# design.net
KiCad netlist of a schematic drawn in EasyEDA Pro
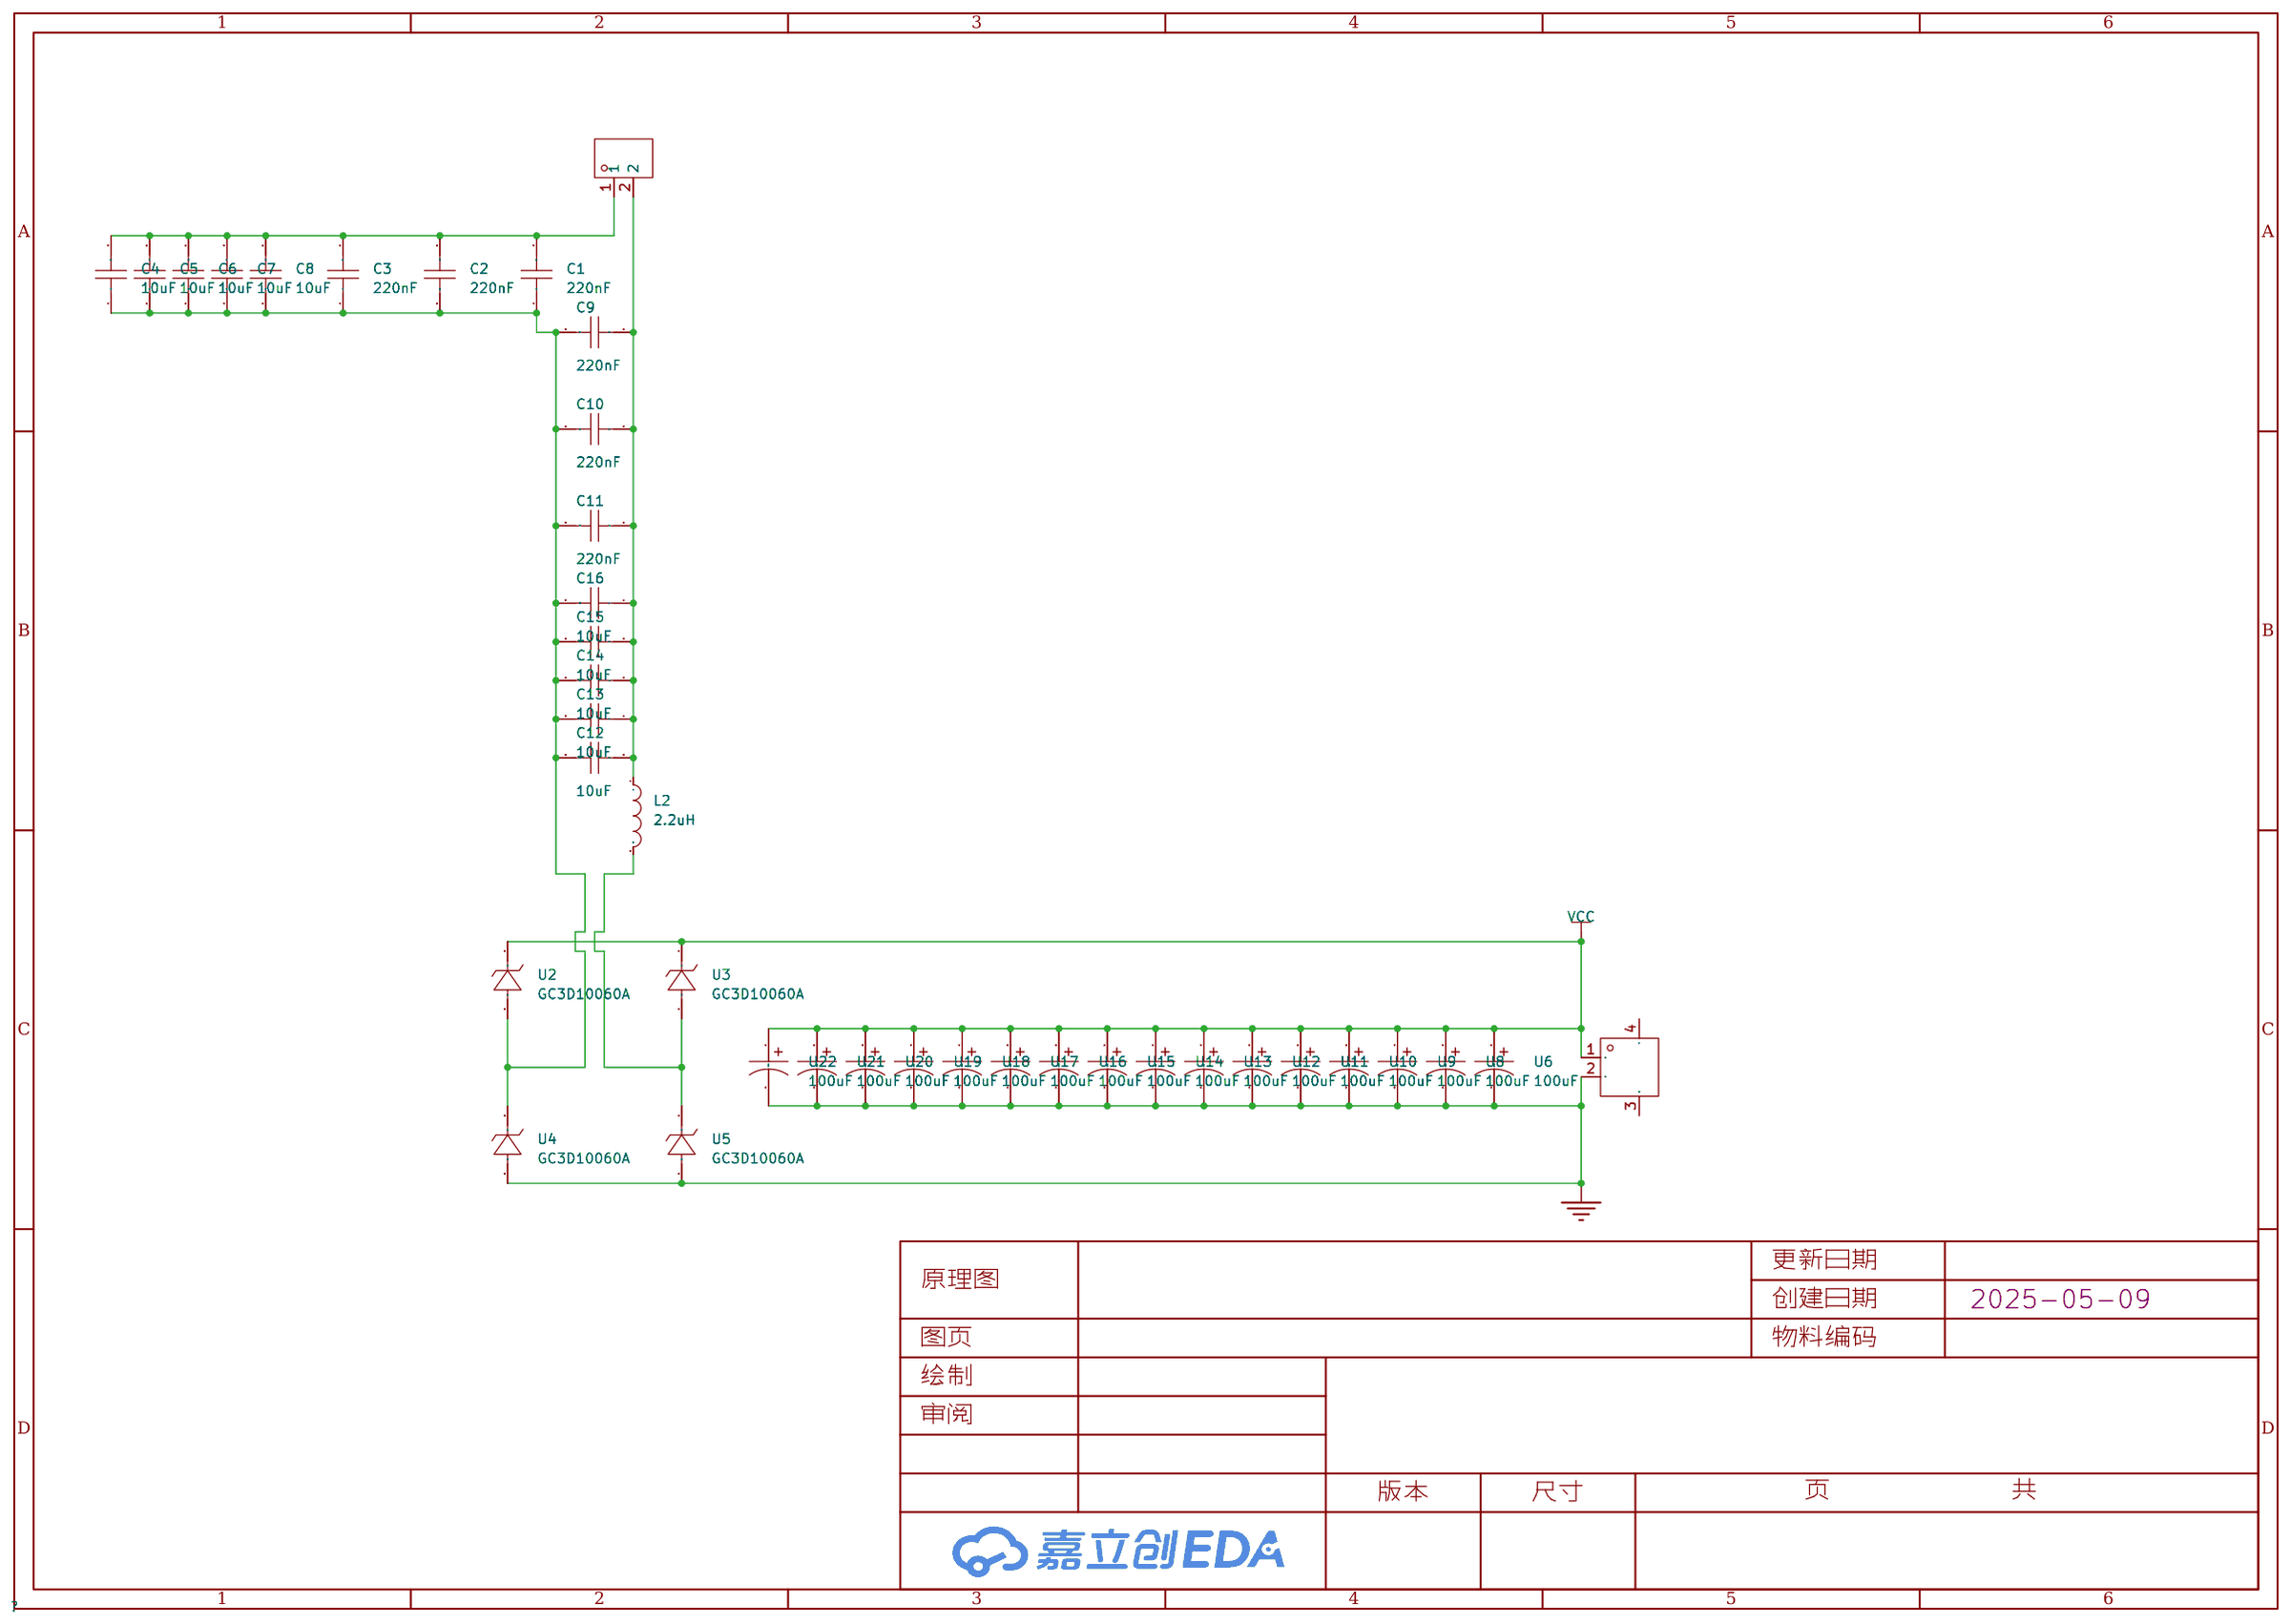
[diagram p0: schematic sheet]

(export (version "E")
  (design (tool "Eeschema 10.0.6"))
  (components
    (comp (ref "C1")
      (value "220nF")
      (footprint "easyedapro:CAP-TH_L12.0-W6.5-P10.00-D1.0")
      (description "容值:220nF;精度:±5%;额定电压:630V;工作温度:-40°C~+105°C;")
      (fields
        (field (name "Manufacturer Part") "MPP224J2J10NN22600")
        (field (name "Manufacturer") "KNSCHA(科尼盛)")
      )
      (libsource (lib "easyedapro") (part "MPP224J2J10NN22600"))
    )
    (comp (ref "C2")
      (value "220nF")
      (footprint "easyedapro:CAP-TH_L12.0-W6.5-P10.00-D1.0")
      (description "容值:220nF;精度:±5%;额定电压:630V;工作温度:-40°C~+105°C;")
      (fields
        (field (name "Manufacturer Part") "MPP224J2J10NN22600")
        (field (name "Manufacturer") "KNSCHA(科尼盛)")
      )
      (libsource (lib "easyedapro") (part "MPP224J2J10NN22600"))
    )
    (comp (ref "C3")
      (value "220nF")
      (footprint "easyedapro:CAP-TH_L12.0-W6.5-P10.00-D1.0")
      (description "容值:220nF;精度:±5%;额定电压:630V;工作温度:-40°C~+105°C;")
      (fields
        (field (name "Manufacturer Part") "MPP224J2J10NN22600")
        (field (name "Manufacturer") "KNSCHA(科尼盛)")
      )
      (libsource (lib "easyedapro") (part "MPP224J2J10NN22600"))
    )
    (comp (ref "C4")
      (value "10uF")
      (footprint "easyedapro:C1206")
      (description "容值:10uF;精度:±10%;额定电压:50V;温度系数:X5R;")
      (fields
        (field (name "Manufacturer Part") "HGC1206R5106K500NSPJ")
        (field (name "Manufacturer") "Chinocera(华瓷)")
      )
      (libsource (lib "easyedapro") (part "HGC1206R5106K500NSPJ"))
    )
    (comp (ref "C5")
      (value "10uF")
      (footprint "easyedapro:C1206")
      (description "容值:10uF;精度:±10%;额定电压:50V;温度系数:X5R;")
      (fields
        (field (name "Manufacturer Part") "HGC1206R5106K500NSPJ")
        (field (name "Manufacturer") "Chinocera(华瓷)")
      )
      (libsource (lib "easyedapro") (part "HGC1206R5106K500NSPJ"))
    )
    (comp (ref "C6")
      (value "10uF")
      (footprint "easyedapro:C1206")
      (description "容值:10uF;精度:±10%;额定电压:50V;温度系数:X5R;")
      (fields
        (field (name "Manufacturer Part") "HGC1206R5106K500NSPJ")
        (field (name "Manufacturer") "Chinocera(华瓷)")
      )
      (libsource (lib "easyedapro") (part "HGC1206R5106K500NSPJ"))
    )
    (comp (ref "C7")
      (value "10uF")
      (footprint "easyedapro:C1206")
      (description "容值:10uF;精度:±10%;额定电压:50V;温度系数:X5R;")
      (fields
        (field (name "Manufacturer Part") "HGC1206R5106K500NSPJ")
        (field (name "Manufacturer") "Chinocera(华瓷)")
      )
      (libsource (lib "easyedapro") (part "HGC1206R5106K500NSPJ"))
    )
    (comp (ref "C8")
      (value "10uF")
      (footprint "easyedapro:C1206")
      (description "容值:10uF;精度:±10%;额定电压:50V;温度系数:X5R;")
      (fields
        (field (name "Manufacturer Part") "HGC1206R5106K500NSPJ")
        (field (name "Manufacturer") "Chinocera(华瓷)")
      )
      (libsource (lib "easyedapro") (part "HGC1206R5106K500NSPJ"))
    )
    (comp (ref "C9")
      (value "220nF")
      (footprint "easyedapro:CAP-TH_L12.0-W6.5-P10.00-D1.0")
      (description "容值:220nF;精度:±5%;额定电压:630V;工作温度:-40°C~+105°C;")
      (fields
        (field (name "Manufacturer Part") "MPP224J2J10NN22600")
        (field (name "Manufacturer") "KNSCHA(科尼盛)")
      )
      (libsource (lib "easyedapro") (part "MPP224J2J10NN22600"))
    )
    (comp (ref "C10")
      (value "220nF")
      (footprint "easyedapro:CAP-TH_L12.0-W6.5-P10.00-D1.0")
      (description "容值:220nF;精度:±5%;额定电压:630V;工作温度:-40°C~+105°C;")
      (fields
        (field (name "Manufacturer Part") "MPP224J2J10NN22600")
        (field (name "Manufacturer") "KNSCHA(科尼盛)")
      )
      (libsource (lib "easyedapro") (part "MPP224J2J10NN22600"))
    )
    (comp (ref "C11")
      (value "220nF")
      (footprint "easyedapro:CAP-TH_L12.0-W6.5-P10.00-D1.0")
      (description "容值:220nF;精度:±5%;额定电压:630V;工作温度:-40°C~+105°C;")
      (fields
        (field (name "Manufacturer Part") "MPP224J2J10NN22600")
        (field (name "Manufacturer") "KNSCHA(科尼盛)")
      )
      (libsource (lib "easyedapro") (part "MPP224J2J10NN22600"))
    )
    (comp (ref "C12")
      (value "10uF")
      (footprint "easyedapro:C1206")
      (description "容值:10uF;精度:±10%;额定电压:50V;温度系数:X5R;")
      (fields
        (field (name "Manufacturer Part") "HGC1206R5106K500NSPJ")
        (field (name "Manufacturer") "Chinocera(华瓷)")
      )
      (libsource (lib "easyedapro") (part "HGC1206R5106K500NSPJ"))
    )
    (comp (ref "C13")
      (value "10uF")
      (footprint "easyedapro:C1206")
      (description "容值:10uF;精度:±10%;额定电压:50V;温度系数:X5R;")
      (fields
        (field (name "Manufacturer Part") "HGC1206R5106K500NSPJ")
        (field (name "Manufacturer") "Chinocera(华瓷)")
      )
      (libsource (lib "easyedapro") (part "HGC1206R5106K500NSPJ"))
    )
    (comp (ref "C14")
      (value "10uF")
      (footprint "easyedapro:C1206")
      (description "容值:10uF;精度:±10%;额定电压:50V;温度系数:X5R;")
      (fields
        (field (name "Manufacturer Part") "HGC1206R5106K500NSPJ")
        (field (name "Manufacturer") "Chinocera(华瓷)")
      )
      (libsource (lib "easyedapro") (part "HGC1206R5106K500NSPJ"))
    )
    (comp (ref "C15")
      (value "10uF")
      (footprint "easyedapro:C1206")
      (description "容值:10uF;精度:±10%;额定电压:50V;温度系数:X5R;")
      (fields
        (field (name "Manufacturer Part") "HGC1206R5106K500NSPJ")
        (field (name "Manufacturer") "Chinocera(华瓷)")
      )
      (libsource (lib "easyedapro") (part "HGC1206R5106K500NSPJ"))
    )
    (comp (ref "C16")
      (value "10uF")
      (footprint "easyedapro:C1206")
      (description "容值:10uF;精度:±10%;额定电压:50V;温度系数:X5R;")
      (fields
        (field (name "Manufacturer Part") "HGC1206R5106K500NSPJ")
        (field (name "Manufacturer") "Chinocera(华瓷)")
      )
      (libsource (lib "easyedapro") (part "HGC1206R5106K500NSPJ"))
    )
    (comp (ref "CN1")
      (value "XT30U-M")
      (footprint "easyedapro:CONN-TH_XT30U-M")
      (description "类别:-;类型1:-;")
      (fields (field (name "Manufacturer") "AMASS(艾迈斯)"))
      (libsource (lib "easyedapro") (part "XT30U-M"))
    )
    (comp (ref "L2")
      (value "2.2uH")
      (footprint "easyedapro:IND-SMD_L11.0-W10.0")
      (description "电感值:2.2uH;精度:±20%;额定电流:13A;饱和电流(Isat):20A;类型:一体成型电感;")
      (fields
        (field (name "Manufacturer Part") "CXP1050-2R2M-AG(2.2uh)")
        (field (name "Manufacturer") "DMBJ(振宝佳)")
      )
      (libsource (lib "easyedapro") (part "CXP1050-2R2M-AG(2.2UH)"))
    )
    (comp (ref "U1")
      (value "XT30PW-F20.G.Y")
      (footprint "easyedapro:CONN-TH_XT30PW-F-1")
      (description "类别:-;类型1:-;")
      (fields (field (name "Manufacturer") "AMASS(艾迈斯)"))
      (libsource (lib "easyedapro") (part "XT30PW-F"))
    )
    (comp (ref "U2")
      (value "GC3D10060A")
      (footprint "easyedapro:TO-220-2_L10.2-W4.5-P5.08-L-A")
      (description "整流电流:30A;正向压降(Vf):1.5V;直流反向耐压(Vr):600V;")
      (fields (field (name "Manufacturer") "SUPSiC(国晶微半导体)"))
      (libsource (lib "easyedapro") (part "GC3D10060A"))
    )
    (comp (ref "U3")
      (value "GC3D10060A")
      (footprint "easyedapro:TO-220-2_L10.2-W4.5-P5.08-L-A")
      (description "整流电流:30A;正向压降(Vf):1.5V;直流反向耐压(Vr):600V;")
      (fields (field (name "Manufacturer") "SUPSiC(国晶微半导体)"))
      (libsource (lib "easyedapro") (part "GC3D10060A"))
    )
    (comp (ref "U4")
      (value "GC3D10060A")
      (footprint "easyedapro:TO-220-2_L10.2-W4.5-P5.08-L-A")
      (description "整流电流:30A;正向压降(Vf):1.5V;直流反向耐压(Vr):600V;")
      (fields (field (name "Manufacturer") "SUPSiC(国晶微半导体)"))
      (libsource (lib "easyedapro") (part "GC3D10060A"))
    )
    (comp (ref "U5")
      (value "GC3D10060A")
      (footprint "easyedapro:TO-220-2_L10.2-W4.5-P5.08-L-A")
      (description "整流电流:30A;正向压降(Vf):1.5V;直流反向耐压(Vr):600V;")
      (fields (field (name "Manufacturer") "SUPSiC(国晶微半导体)"))
      (libsource (lib "easyedapro") (part "GC3D10060A"))
    )
    (comp (ref "U6")
      (value "100uF")
      (footprint "easyedapro:CAP-TH_BD10.0-P5.00-D0.6-FD")
      (description "容值:100uF;精度:±20%;额定电压:100V;纹波电流:420mA@100kHz;等效串联电阻(ESR):420mΩ@100kHz;")
      (fields (field (name "Manufacturer Part") "01EC0961") (field (name "Manufacturer") "KNSCHA(科尼盛)"))
      (libsource (lib "easyedapro") (part "01EC0961"))
    )
    (comp (ref "U8")
      (value "100uF")
      (footprint "easyedapro:CAP-TH_BD10.0-P5.00-D0.6-FD")
      (description "容值:100uF;精度:±20%;额定电压:100V;纹波电流:420mA@100kHz;等效串联电阻(ESR):420mΩ@100kHz;")
      (fields (field (name "Manufacturer Part") "01EC0961") (field (name "Manufacturer") "KNSCHA(科尼盛)"))
      (libsource (lib "easyedapro") (part "01EC0961"))
    )
    (comp (ref "U9")
      (value "100uF")
      (footprint "easyedapro:CAP-TH_BD10.0-P5.00-D0.6-FD")
      (description "容值:100uF;精度:±20%;额定电压:100V;纹波电流:420mA@100kHz;等效串联电阻(ESR):420mΩ@100kHz;")
      (fields (field (name "Manufacturer Part") "01EC0961") (field (name "Manufacturer") "KNSCHA(科尼盛)"))
      (libsource (lib "easyedapro") (part "01EC0961"))
    )
    (comp (ref "U10")
      (value "100uF")
      (footprint "easyedapro:CAP-TH_BD10.0-P5.00-D0.6-FD")
      (description "容值:100uF;精度:±20%;额定电压:100V;纹波电流:420mA@100kHz;等效串联电阻(ESR):420mΩ@100kHz;")
      (fields (field (name "Manufacturer Part") "01EC0961") (field (name "Manufacturer") "KNSCHA(科尼盛)"))
      (libsource (lib "easyedapro") (part "01EC0961"))
    )
    (comp (ref "U11")
      (value "100uF")
      (footprint "easyedapro:CAP-TH_BD10.0-P5.00-D0.6-FD")
      (description "容值:100uF;精度:±20%;额定电压:100V;纹波电流:420mA@100kHz;等效串联电阻(ESR):420mΩ@100kHz;")
      (fields (field (name "Manufacturer Part") "01EC0961") (field (name "Manufacturer") "KNSCHA(科尼盛)"))
      (libsource (lib "easyedapro") (part "01EC0961"))
    )
    (comp (ref "U12")
      (value "100uF")
      (footprint "easyedapro:CAP-TH_BD10.0-P5.00-D0.6-FD")
      (description "容值:100uF;精度:±20%;额定电压:100V;纹波电流:420mA@100kHz;等效串联电阻(ESR):420mΩ@100kHz;")
      (fields (field (name "Manufacturer Part") "01EC0961") (field (name "Manufacturer") "KNSCHA(科尼盛)"))
      (libsource (lib "easyedapro") (part "01EC0961"))
    )
    (comp (ref "U13")
      (value "100uF")
      (footprint "easyedapro:CAP-TH_BD10.0-P5.00-D0.6-FD")
      (description "容值:100uF;精度:±20%;额定电压:100V;纹波电流:420mA@100kHz;等效串联电阻(ESR):420mΩ@100kHz;")
      (fields (field (name "Manufacturer Part") "01EC0961") (field (name "Manufacturer") "KNSCHA(科尼盛)"))
      (libsource (lib "easyedapro") (part "01EC0961"))
    )
    (comp (ref "U14")
      (value "100uF")
      (footprint "easyedapro:CAP-TH_BD10.0-P5.00-D0.6-FD")
      (description "容值:100uF;精度:±20%;额定电压:100V;纹波电流:420mA@100kHz;等效串联电阻(ESR):420mΩ@100kHz;")
      (fields (field (name "Manufacturer Part") "01EC0961") (field (name "Manufacturer") "KNSCHA(科尼盛)"))
      (libsource (lib "easyedapro") (part "01EC0961"))
    )
    (comp (ref "U15")
      (value "100uF")
      (footprint "easyedapro:CAP-TH_BD10.0-P5.00-D0.6-FD")
      (description "容值:100uF;精度:±20%;额定电压:100V;纹波电流:420mA@100kHz;等效串联电阻(ESR):420mΩ@100kHz;")
      (fields (field (name "Manufacturer Part") "01EC0961") (field (name "Manufacturer") "KNSCHA(科尼盛)"))
      (libsource (lib "easyedapro") (part "01EC0961"))
    )
    (comp (ref "U16")
      (value "100uF")
      (footprint "easyedapro:CAP-TH_BD10.0-P5.00-D0.6-FD")
      (description "容值:100uF;精度:±20%;额定电压:100V;纹波电流:420mA@100kHz;等效串联电阻(ESR):420mΩ@100kHz;")
      (fields (field (name "Manufacturer Part") "01EC0961") (field (name "Manufacturer") "KNSCHA(科尼盛)"))
      (libsource (lib "easyedapro") (part "01EC0961"))
    )
    (comp (ref "U17")
      (value "100uF")
      (footprint "easyedapro:CAP-TH_BD10.0-P5.00-D0.6-FD")
      (description "容值:100uF;精度:±20%;额定电压:100V;纹波电流:420mA@100kHz;等效串联电阻(ESR):420mΩ@100kHz;")
      (fields (field (name "Manufacturer Part") "01EC0961") (field (name "Manufacturer") "KNSCHA(科尼盛)"))
      (libsource (lib "easyedapro") (part "01EC0961"))
    )
    (comp (ref "U18")
      (value "100uF")
      (footprint "easyedapro:CAP-TH_BD10.0-P5.00-D0.6-FD")
      (description "容值:100uF;精度:±20%;额定电压:100V;纹波电流:420mA@100kHz;等效串联电阻(ESR):420mΩ@100kHz;")
      (fields (field (name "Manufacturer Part") "01EC0961") (field (name "Manufacturer") "KNSCHA(科尼盛)"))
      (libsource (lib "easyedapro") (part "01EC0961"))
    )
    (comp (ref "U19")
      (value "100uF")
      (footprint "easyedapro:CAP-TH_BD10.0-P5.00-D0.6-FD")
      (description "容值:100uF;精度:±20%;额定电压:100V;纹波电流:420mA@100kHz;等效串联电阻(ESR):420mΩ@100kHz;")
      (fields (field (name "Manufacturer Part") "01EC0961") (field (name "Manufacturer") "KNSCHA(科尼盛)"))
      (libsource (lib "easyedapro") (part "01EC0961"))
    )
    (comp (ref "U20")
      (value "100uF")
      (footprint "easyedapro:CAP-TH_BD10.0-P5.00-D0.6-FD")
      (description "容值:100uF;精度:±20%;额定电压:100V;纹波电流:420mA@100kHz;等效串联电阻(ESR):420mΩ@100kHz;")
      (fields (field (name "Manufacturer Part") "01EC0961") (field (name "Manufacturer") "KNSCHA(科尼盛)"))
      (libsource (lib "easyedapro") (part "01EC0961"))
    )
    (comp (ref "U21")
      (value "100uF")
      (footprint "easyedapro:CAP-TH_BD10.0-P5.00-D0.6-FD")
      (description "容值:100uF;精度:±20%;额定电压:100V;纹波电流:420mA@100kHz;等效串联电阻(ESR):420mΩ@100kHz;")
      (fields (field (name "Manufacturer Part") "01EC0961") (field (name "Manufacturer") "KNSCHA(科尼盛)"))
      (libsource (lib "easyedapro") (part "01EC0961"))
    )
    (comp (ref "U22")
      (value "100uF")
      (footprint "easyedapro:CAP-TH_BD10.0-P5.00-D0.6-FD")
      (description "容值:100uF;精度:±20%;额定电压:100V;纹波电流:420mA@100kHz;等效串联电阻(ESR):420mΩ@100kHz;")
      (fields (field (name "Manufacturer Part") "01EC0961") (field (name "Manufacturer") "KNSCHA(科尼盛)"))
      (libsource (lib "easyedapro") (part "01EC0961"))
    )
  )
  (nets
    (net (code "1") (name "GND") (class "Default")
      (node (ref "U1") (pin "2") (pinfunction "2_2") (pintype "unspecified"))
      (node (ref "U10") (pin "2") (pinfunction "2_2") (pintype "unspecified"))
      (node (ref "U11") (pin "2") (pinfunction "2_2") (pintype "unspecified"))
      (node (ref "U12") (pin "2") (pinfunction "2_2") (pintype "unspecified"))
      (node (ref "U13") (pin "2") (pinfunction "2_2") (pintype "unspecified"))
      (node (ref "U14") (pin "2") (pinfunction "2_2") (pintype "unspecified"))
      (node (ref "U15") (pin "2") (pinfunction "2_2") (pintype "unspecified"))
      (node (ref "U16") (pin "2") (pinfunction "2_2") (pintype "unspecified"))
      (node (ref "U17") (pin "2") (pinfunction "2_2") (pintype "unspecified"))
      (node (ref "U18") (pin "2") (pinfunction "2_2") (pintype "unspecified"))
      (node (ref "U19") (pin "2") (pinfunction "2_2") (pintype "unspecified"))
      (node (ref "U20") (pin "2") (pinfunction "2_2") (pintype "unspecified"))
      (node (ref "U21") (pin "2") (pinfunction "2_2") (pintype "unspecified"))
      (node (ref "U22") (pin "2") (pinfunction "2_2") (pintype "unspecified"))
      (node (ref "U4") (pin "3") (pinfunction "A_3") (pintype "unspecified"))
      (node (ref "U5") (pin "3") (pinfunction "A_3") (pintype "unspecified"))
      (node (ref "U6") (pin "2") (pinfunction "2_2") (pintype "unspecified"))
      (node (ref "U8") (pin "2") (pinfunction "2_2") (pintype "unspecified"))
      (node (ref "U9") (pin "2") (pinfunction "2_2") (pintype "unspecified"))
    )
    (net (code "2") (name "Net-(C1-Pad2)") (class "Default")
      (node (ref "C1") (pin "2") (pinfunction "2_2") (pintype "unspecified"))
      (node (ref "C2") (pin "2") (pinfunction "2_2") (pintype "unspecified"))
      (node (ref "C3") (pin "2") (pinfunction "2_2") (pintype "unspecified"))
      (node (ref "C4") (pin "2") (pinfunction "2_2") (pintype "unspecified"))
      (node (ref "C5") (pin "2") (pinfunction "2_2") (pintype "unspecified"))
      (node (ref "C6") (pin "2") (pinfunction "2_2") (pintype "unspecified"))
      (node (ref "C7") (pin "2") (pinfunction "2_2") (pintype "unspecified"))
      (node (ref "C8") (pin "2") (pinfunction "2_2") (pintype "unspecified"))
      (node (ref "CN1") (pin "1") (pinfunction "1_1") (pintype "unspecified"))
    )
    (net (code "3") (name "Net-(C10-Pad1)") (class "Default")
      (node (ref "C10") (pin "1") (pinfunction "1_1") (pintype "unspecified"))
      (node (ref "C11") (pin "1") (pinfunction "1_1") (pintype "unspecified"))
      (node (ref "C12") (pin "1") (pinfunction "1_1") (pintype "unspecified"))
      (node (ref "C13") (pin "1") (pinfunction "1_1") (pintype "unspecified"))
      (node (ref "C14") (pin "1") (pinfunction "1_1") (pintype "unspecified"))
      (node (ref "C15") (pin "1") (pinfunction "1_1") (pintype "unspecified"))
      (node (ref "C16") (pin "1") (pinfunction "1_1") (pintype "unspecified"))
      (node (ref "C9") (pin "1") (pinfunction "1_1") (pintype "unspecified"))
      (node (ref "CN1") (pin "2") (pinfunction "2_2") (pintype "unspecified"))
      (node (ref "L2") (pin "1") (pinfunction "1_1") (pintype "unspecified"))
    )
    (net (code "4") (name "Net-(U2-A)") (class "Default")
      (node (ref "C1") (pin "1") (pinfunction "1_1") (pintype "unspecified"))
      (node (ref "C10") (pin "2") (pinfunction "2_2") (pintype "unspecified"))
      (node (ref "C11") (pin "2") (pinfunction "2_2") (pintype "unspecified"))
      (node (ref "C12") (pin "2") (pinfunction "2_2") (pintype "unspecified"))
      (node (ref "C13") (pin "2") (pinfunction "2_2") (pintype "unspecified"))
      (node (ref "C14") (pin "2") (pinfunction "2_2") (pintype "unspecified"))
      (node (ref "C15") (pin "2") (pinfunction "2_2") (pintype "unspecified"))
      (node (ref "C16") (pin "2") (pinfunction "2_2") (pintype "unspecified"))
      (node (ref "C2") (pin "1") (pinfunction "1_1") (pintype "unspecified"))
      (node (ref "C3") (pin "1") (pinfunction "1_1") (pintype "unspecified"))
      (node (ref "C4") (pin "1") (pinfunction "1_1") (pintype "unspecified"))
      (node (ref "C5") (pin "1") (pinfunction "1_1") (pintype "unspecified"))
      (node (ref "C6") (pin "1") (pinfunction "1_1") (pintype "unspecified"))
      (node (ref "C7") (pin "1") (pinfunction "1_1") (pintype "unspecified"))
      (node (ref "C8") (pin "1") (pinfunction "1_1") (pintype "unspecified"))
      (node (ref "C9") (pin "2") (pinfunction "2_2") (pintype "unspecified"))
      (node (ref "U2") (pin "3") (pinfunction "A_3") (pintype "unspecified"))
      (node (ref "U4") (pin "1") (pinfunction "K_1") (pintype "unspecified"))
    )
    (net (code "5") (name "Net-(U3-A)") (class "Default")
      (node (ref "L2") (pin "2") (pinfunction "2_2") (pintype "unspecified"))
      (node (ref "U3") (pin "3") (pinfunction "A_3") (pintype "unspecified"))
      (node (ref "U5") (pin "1") (pinfunction "K_1") (pintype "unspecified"))
    )
    (net (code "6") (name "VCC") (class "Default")
      (node (ref "U1") (pin "1") (pinfunction "1_1") (pintype "unspecified"))
      (node (ref "U10") (pin "1") (pinfunction "1_1") (pintype "unspecified"))
      (node (ref "U11") (pin "1") (pinfunction "1_1") (pintype "unspecified"))
      (node (ref "U12") (pin "1") (pinfunction "1_1") (pintype "unspecified"))
      (node (ref "U13") (pin "1") (pinfunction "1_1") (pintype "unspecified"))
      (node (ref "U14") (pin "1") (pinfunction "1_1") (pintype "unspecified"))
      (node (ref "U15") (pin "1") (pinfunction "1_1") (pintype "unspecified"))
      (node (ref "U16") (pin "1") (pinfunction "1_1") (pintype "unspecified"))
      (node (ref "U17") (pin "1") (pinfunction "1_1") (pintype "unspecified"))
      (node (ref "U18") (pin "1") (pinfunction "1_1") (pintype "unspecified"))
      (node (ref "U19") (pin "1") (pinfunction "1_1") (pintype "unspecified"))
      (node (ref "U2") (pin "1") (pinfunction "K_1") (pintype "unspecified"))
      (node (ref "U20") (pin "1") (pinfunction "1_1") (pintype "unspecified"))
      (node (ref "U21") (pin "1") (pinfunction "1_1") (pintype "unspecified"))
      (node (ref "U22") (pin "1") (pinfunction "1_1") (pintype "unspecified"))
      (node (ref "U3") (pin "1") (pinfunction "K_1") (pintype "unspecified"))
      (node (ref "U6") (pin "1") (pinfunction "1_1") (pintype "unspecified"))
      (node (ref "U8") (pin "1") (pinfunction "1_1") (pintype "unspecified"))
      (node (ref "U9") (pin "1") (pinfunction "1_1") (pintype "unspecified"))
    )
    (net (code "7") (name "unconnected-(U1-Pad3)") (class "Default")
      (node (ref "U1") (pin "3") (pinfunction "3_3") (pintype "unspecified"))
    )
    (net (code "8") (name "unconnected-(U1-Pad4)") (class "Default")
      (node (ref "U1") (pin "4") (pinfunction "4_4") (pintype "unspecified"))
    )
  )
)
